# DIO_MCX_Supply.net
KiCad netlist of a schematic drawn in Altium Designer
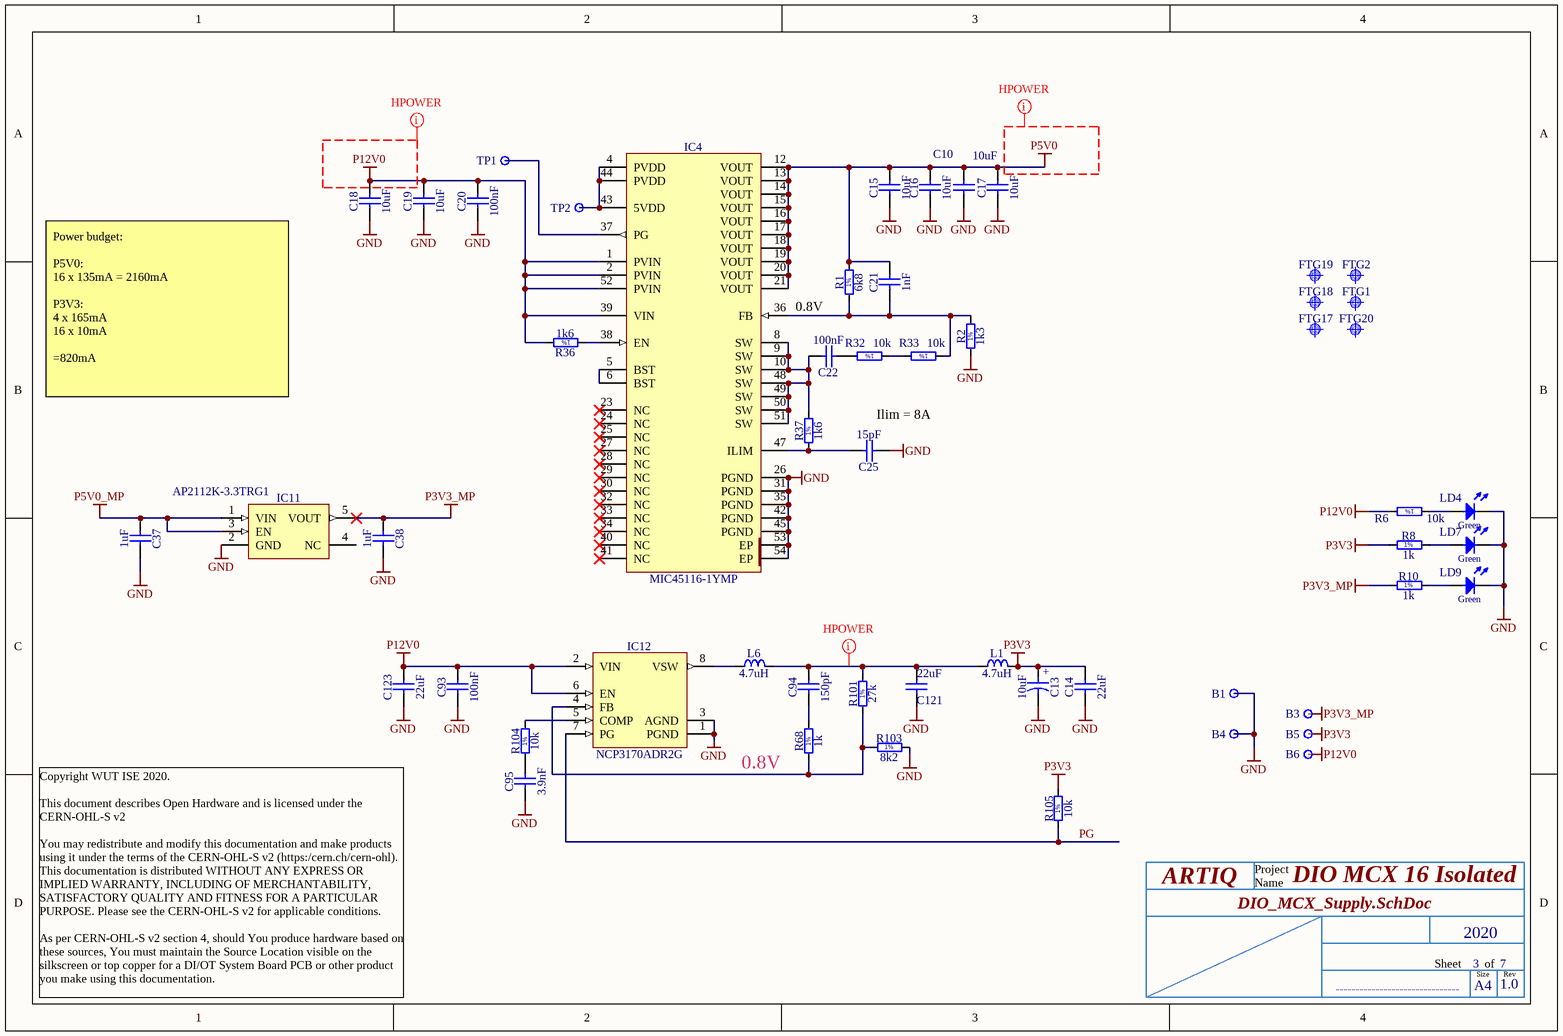
[diagram p0: DIO_MCX_Supply.SchDoc]

(export (version "E")
  (design (tool "Eeschema 10.0.6"))
  (components
    (comp (ref "B1")
      (value "Plated Hole")
      (footprint "c130h60")
      (description "Single Terminal Socket")
      (fields (field (name "PART NUMBER") "PLATED_HOLE0.6_PAD1.3") (field (name "AUTHOR") "CERN DEM MR"))
      (libsource (lib "Eletro-mechanical") (part "Single Terminal Socket"))
    )
    (comp (ref "B3")
      (value "Plated Hole")
      (footprint "c130h60")
      (description "Single Terminal Socket")
      (fields (field (name "PART NUMBER") "PLATED_HOLE0.6_PAD1.3") (field (name "AUTHOR") "CERN DEM MR"))
      (libsource (lib "Eletro-mechanical") (part "Single Terminal Socket"))
    )
    (comp (ref "B4")
      (value "Plated Hole")
      (footprint "c130h60")
      (description "Single Terminal Socket")
      (fields (field (name "PART NUMBER") "PLATED_HOLE0.6_PAD1.3") (field (name "AUTHOR") "CERN DEM MR"))
      (libsource (lib "Eletro-mechanical") (part "Single Terminal Socket"))
    )
    (comp (ref "B5")
      (value "Plated Hole")
      (footprint "c130h60")
      (description "Single Terminal Socket")
      (fields (field (name "PART NUMBER") "PLATED_HOLE0.6_PAD1.3") (field (name "AUTHOR") "CERN DEM MR"))
      (libsource (lib "Eletro-mechanical") (part "Single Terminal Socket"))
    )
    (comp (ref "B6")
      (value "Plated Hole")
      (footprint "c130h60")
      (description "Single Terminal Socket")
      (fields (field (name "PART NUMBER") "PLATED_HOLE0.6_PAD1.3") (field (name "AUTHOR") "CERN DEM MR"))
      (libsource (lib "Eletro-mechanical") (part "Single Terminal Socket"))
    )
    (comp (ref "C10")
      (value "10uF")
      (footprint "CAPC2012X135N")
      (description "Non-polarised capacitor")
      (fields
        (field (name "PART NUMBER") "CC0805_10UF_16V_10%_X5R")
        (field (name "VOLTAGE") "16V")
        (field (name "AUTHOR") "CERN DEM JLC")
      )
      (libsource (lib "Capacitors") (part "Capacitor - non polarized"))
    )
    (comp (ref "C13")
      (value "10uF")
      (footprint "CAPAE430X540N")
      (description "Polarised capacitor")
      (fields
        (field (name "PART NUMBER") "CAE430-540_10UF_16V_20%")
        (field (name "VOLTAGE") "16V")
        (field (name "AUTHOR") "CERN DEM JLC")
      )
      (libsource (lib "Capacitors") (part "Capacitor - polarized"))
    )
    (comp (ref "C14")
      (value "22uF")
      (footprint "CAPC2012X135N")
      (description "Non-polarised capacitor")
      (fields
        (field (name "PART NUMBER") "CC0805_22UF_16V_10%_X5R")
        (field (name "VOLTAGE") "16V")
        (field (name "AUTHOR") "CERN DEM JLC")
      )
      (libsource (lib "Capacitors") (part "Capacitor - non polarized"))
    )
    (comp (ref "C15")
      (value "10uF")
      (footprint "CAPC2012X135N")
      (description "Non-polarised capacitor")
      (fields
        (field (name "PART NUMBER") "CC0805_10UF_16V_10%_X5R")
        (field (name "VOLTAGE") "16V")
        (field (name "AUTHOR") "CERN DEM JLC")
      )
      (libsource (lib "Capacitors") (part "Capacitor - non polarized"))
    )
    (comp (ref "C16")
      (value "10uF")
      (footprint "CAPC2012X135N")
      (description "Non-polarised capacitor")
      (fields
        (field (name "PART NUMBER") "CC0805_10UF_16V_10%_X5R")
        (field (name "VOLTAGE") "16V")
        (field (name "AUTHOR") "CERN DEM JLC")
      )
      (libsource (lib "Capacitors") (part "Capacitor - non polarized"))
    )
    (comp (ref "C17")
      (value "10uF")
      (footprint "CAPC2012X135N")
      (description "Non-polarised capacitor")
      (fields
        (field (name "PART NUMBER") "CC0805_10UF_16V_10%_X5R")
        (field (name "VOLTAGE") "16V")
        (field (name "AUTHOR") "CERN DEM JLC")
      )
      (libsource (lib "Capacitors") (part "Capacitor - non polarized"))
    )
    (comp (ref "C18")
      (value "10uF")
      (footprint "CAPC2012X135N")
      (description "Non-polarised capacitor")
      (fields
        (field (name "PART NUMBER") "CC0805_10UF_16V_10%_X5R")
        (field (name "VOLTAGE") "16V")
        (field (name "AUTHOR") "CERN DEM JLC")
      )
      (libsource (lib "Capacitors") (part "Capacitor - non polarized"))
    )
    (comp (ref "C19")
      (value "10uF")
      (footprint "CAPC2012X135N")
      (description "Non-polarised capacitor")
      (fields
        (field (name "PART NUMBER") "CC0805_10UF_16V_10%_X5R")
        (field (name "VOLTAGE") "16V")
        (field (name "AUTHOR") "CERN DEM JLC")
      )
      (libsource (lib "Capacitors") (part "Capacitor - non polarized"))
    )
    (comp (ref "C20")
      (value "100nF")
      (footprint "CAPC1005X55N")
      (description "Non-polarised capacitor")
      (fields
        (field (name "PART NUMBER") "CC0402_100NF_16V_10%_X5R")
        (field (name "VOLTAGE") "16V")
        (field (name "AUTHOR") "CERN DEM JLC")
      )
      (libsource (lib "Capacitors") (part "Capacitor - non polarized"))
    )
    (comp (ref "C21")
      (value "1nF")
      (footprint "CAPC1608X87N")
      (description "Non-polarised capacitor")
      (fields
        (field (name "PART NUMBER") "CC0603_1NF_100V_10%_X7R")
        (field (name "VOLTAGE") "100V")
        (field (name "AUTHOR") "CERN DEM JLC")
      )
      (libsource (lib "Capacitors") (part "Capacitor - non polarized"))
    )
    (comp (ref "C22")
      (value "100nF")
      (footprint "CAPC1005X55N")
      (description "Non-polarised capacitor")
      (fields
        (field (name "PART NUMBER") "CC0402_100NF_16V_10%_X5R")
        (field (name "VOLTAGE") "16V")
        (field (name "AUTHOR") "CERN DEM JLC")
      )
      (libsource (lib "Capacitors") (part "Capacitor - non polarized"))
    )
    (comp (ref "C25")
      (value "15pF")
      (footprint "CAPC1005X55N")
      (description "Non-polarised capacitor")
      (fields
        (field (name "PART NUMBER") "CC0402_15PF_50V_5%_C0G")
        (field (name "VOLTAGE") "50V")
        (field (name "AUTHOR") "CERN DEM JLC")
      )
      (libsource (lib "Capacitors") (part "Capacitor - non polarized"))
    )
    (comp (ref "C37")
      (value "1uF")
      (footprint "CAPC1005X55N")
      (description "Non-polarised capacitor")
      (fields
        (field (name "PART NUMBER") "CC0402_1UF_16V_10%_X5R")
        (field (name "VOLTAGE") "16V")
        (field (name "AUTHOR") "CERN DEM JLC")
      )
      (libsource (lib "Capacitors") (part "Capacitor - non polarized"))
    )
    (comp (ref "C38")
      (value "1uF")
      (footprint "CAPC1005X55N")
      (description "Non-polarised capacitor")
      (fields
        (field (name "PART NUMBER") "CC0402_1UF_16V_10%_X5R")
        (field (name "VOLTAGE") "16V")
        (field (name "AUTHOR") "CERN DEM JLC")
      )
      (libsource (lib "Capacitors") (part "Capacitor - non polarized"))
    )
    (comp (ref "C93")
      (value "100nF")
      (footprint "CAPC1005X55N")
      (description "Non-polarised capacitor")
      (fields
        (field (name "PART NUMBER") "CC0402_100NF_16V_10%_X5R")
        (field (name "VOLTAGE") "16V")
        (field (name "AUTHOR") "CERN DEM JLC")
      )
      (libsource (lib "Capacitors") (part "Capacitor - non polarized"))
    )
    (comp (ref "C94")
      (value "150pF")
      (footprint "CAPC1608X87N")
      (description "Non-polarised capacitor")
      (fields
        (field (name "PART NUMBER") "CC0603_150PF_50V_1%_NP0")
        (field (name "VOLTAGE") "50V")
        (field (name "AUTHOR") "CERN DEM MR")
      )
      (libsource (lib "Capacitors") (part "Capacitor - non polarized"))
    )
    (comp (ref "C95")
      (value "3.9nF")
      (footprint "CAPC1608X87N")
      (description "Non-polarised capacitor")
      (fields
        (field (name "PART NUMBER") "CC0603_3.9NF_50V_5%_X7R")
        (field (name "VOLTAGE") "50V")
        (field (name "AUTHOR") "CERN DEM JLC")
      )
      (libsource (lib "Capacitors") (part "Capacitor - non polarized"))
    )
    (comp (ref "C121")
      (value "22uF")
      (footprint "CAPC2012X135N")
      (description "Non-polarised capacitor")
      (fields
        (field (name "PART NUMBER") "CC0805_22UF_16V_10%_X5R")
        (field (name "VOLTAGE") "16V")
        (field (name "AUTHOR") "CERN DEM JLC")
      )
      (libsource (lib "Capacitors") (part "Capacitor - non polarized"))
    )
    (comp (ref "C123")
      (value "22uF")
      (footprint "CAPC2012X135N")
      (description "Non-polarised capacitor")
      (fields
        (field (name "PART NUMBER") "CC0805_22UF_16V_10%_X5R")
        (field (name "VOLTAGE") "16V")
        (field (name "AUTHOR") "CERN DEM JLC")
      )
      (libsource (lib "Capacitors") (part "Capacitor - non polarized"))
    )
    (comp (ref "FTG1")
      (value "Use only in PCB")
      (footprint "FIDUCIAL_TOP_C100-200")
      (description "Fiducial Target")
      (fields (field (name "PART NUMBER") "FIDUCIAL_TARGET_C100-200") (field (name "AUTHOR") "CERN DEM JLC"))
      (libsource (lib "Eletro-mechanical") (part "Fiducial Target"))
    )
    (comp (ref "FTG2")
      (value "Use only in PCB")
      (footprint "FIDUCIAL_TOP_C100-200")
      (description "Fiducial Target")
      (fields (field (name "PART NUMBER") "FIDUCIAL_TARGET_C100-200") (field (name "AUTHOR") "CERN DEM JLC"))
      (libsource (lib "Eletro-mechanical") (part "Fiducial Target"))
    )
    (comp (ref "FTG17")
      (value "Use only in PCB")
      (footprint "FIDUCIAL_TOP_C100-200")
      (description "Fiducial Target")
      (fields (field (name "PART NUMBER") "FIDUCIAL_TARGET_C100-200") (field (name "AUTHOR") "CERN DEM JLC"))
      (libsource (lib "Eletro-mechanical") (part "Fiducial Target"))
    )
    (comp (ref "FTG18")
      (value "Use only in PCB")
      (footprint "FIDUCIAL_TOP_S100-200")
      (description "Fiducial Target")
      (fields (field (name "PART NUMBER") "FIDUCIAL_TARGET_S100-200") (field (name "AUTHOR") "CERN DEM JLC"))
      (libsource (lib "Eletro-mechanical") (part "Fiducial Target"))
    )
    (comp (ref "FTG19")
      (value "Use only in PCB")
      (footprint "FIDUCIAL_TOP_S100-200")
      (description "Fiducial Target")
      (fields (field (name "PART NUMBER") "FIDUCIAL_TARGET_S100-200") (field (name "AUTHOR") "CERN DEM JLC"))
      (libsource (lib "Eletro-mechanical") (part "Fiducial Target"))
    )
    (comp (ref "FTG20")
      (value "Use only in PCB")
      (footprint "FIDUCIAL_TOP_S100-200")
      (description "Fiducial Target")
      (fields (field (name "PART NUMBER") "FIDUCIAL_TARGET_S100-200") (field (name "AUTHOR") "CERN DEM JLC"))
      (libsource (lib "Eletro-mechanical") (part "Fiducial Target"))
    )
    (comp (ref "IC4")
      (value "MIC45116-1YMP")
      (footprint "MICROCHIP_H3QFN88-52LD-PL-3")
      (description "0.8V to 85% PVIN (4.75-19V), 6A Synchronous Step-Down Regulator Module")
      (fields (field (name "MANUFACTURER") "MICROCHIP TECHNOLOGY") (field (name "AUTHOR") "CERN DEM JMW"))
      (libsource (lib "ICs And Semiconductors") (part "MIC45116"))
    )
    (comp (ref "IC11")
      (value "AP2112K-3.3TRG1")
      (footprint "SOT95P285X140-5N")
      (description "600mA CMOS Low Dropout Linear Regulator with Enable")
      (fields (field (name "MANUFACTURER") "DIODES INCORPORATED") (field (name "AUTHOR") "CERN DEM MR"))
      (libsource (lib "ICs And Semiconductors") (part "AP2112K"))
    )
    (comp (ref "IC12")
      (value "NCP3170ADR2G")
      (footprint "SOIC127P600X175-8N")
      (description "Synchronous PWM Switching Converter")
      (fields (field (name "MANUFACTURER") "ON SEMICONDUCTOR") (field (name "AUTHOR") "CERN DEM MR"))
      (libsource (lib "ICs And Semiconductors") (part "NCP3170ADR2G"))
    )
    (comp (ref "L1")
      (value "4.7uH")
      (footprint "IND_BOURNS_SRU8043")
      (description "Power Shielded  4.7uH 30% 4.6A")
      (fields
        (field (name "PART NUMBER") "IND_4.7UH_30%_BOURNS_SRU8043")
        (field (name "POWER") "4.6A")
        (field (name "AUTHOR") "GK")
      )
      (libsource (lib "Inductors_Transformers") (part "IND_4.7UH_30%_BOURNS_SRU8043"))
    )
    (comp (ref "L6")
      (value "4.7uH")
      (footprint "IND_BOURNS_SRU8043")
      (description "Power Shielded  4.7uH 30% 4.6A")
      (fields
        (field (name "PART NUMBER") "IND_4.7UH_30%_BOURNS_SRU8043")
        (field (name "POWER") "4.6A")
        (field (name "AUTHOR") "GK")
      )
      (libsource (lib "Inductors_Transformers") (part "IND_4.7UH_30%_BOURNS_SRU8043"))
    )
    (comp (ref "LD4")
      (value "Green")
      (footprint "LED_KINGBRIGHT_KPH-1608CGCK")
      (description "LED Green 1C 2A")
      (fields
        (field (name "PART NUMBER") "LED_KINGBRIGHT_KPH-1608CGCK")
        (field (name "MANUFACTURER") "KINGBRIGHT")
        (field (name "AUTHOR") "CERN DEM JLC")
      )
      (libsource (lib "ICs And Semiconductors") (part "LED Green 1C 2A"))
    )
    (comp (ref "LD7")
      (value "Green")
      (footprint "LED_KINGBRIGHT_KPH-1608CGCK")
      (description "LED Green 1C 2A")
      (fields
        (field (name "PART NUMBER") "LED_KINGBRIGHT_KPH-1608CGCK")
        (field (name "MANUFACTURER") "KINGBRIGHT")
        (field (name "AUTHOR") "CERN DEM JLC")
      )
      (libsource (lib "ICs And Semiconductors") (part "LED Green 1C 2A"))
    )
    (comp (ref "LD9")
      (value "Green")
      (footprint "LED_KINGBRIGHT_KPH-1608CGCK")
      (description "LED Green 1C 2A")
      (fields
        (field (name "PART NUMBER") "LED_KINGBRIGHT_KPH-1608CGCK")
        (field (name "MANUFACTURER") "KINGBRIGHT")
        (field (name "AUTHOR") "CERN DEM JLC")
      )
      (libsource (lib "ICs And Semiconductors") (part "LED Green 1C 2A"))
    )
    (comp (ref "R1")
      (value "6k8")
      (footprint "RESC1005X40N")
      (description "Resistor - 1%")
      (fields
        (field (name "PART NUMBER") "R0402_6K8_1%_0.0625W_100PPM")
        (field (name "POWER") "0.0625W")
        (field (name "AUTHOR") "CERN DEM JLC")
      )
      (libsource (lib "Resistors") (part "Resistor - 1%"))
    )
    (comp (ref "R2")
      (value "1k3")
      (footprint "RESC1608X55N")
      (description "Resistor - 1%")
      (fields
        (field (name "PART NUMBER") "R0603_1K3_1%_0.1W_100PPM")
        (field (name "POWER") "0.1W")
        (field (name "AUTHOR") "CERN DEM JLC")
      )
      (libsource (lib "Resistors") (part "Resistor - 1%"))
    )
    (comp (ref "R6")
      (value "10k")
      (footprint "RESC1005X40N")
      (description "Resistor - 1%")
      (fields
        (field (name "PART NUMBER") "R0402_10K_1%_0.0625W_100PPM")
        (field (name "POWER") "0.0625W")
        (field (name "AUTHOR") "CERN DEM JLC")
      )
      (libsource (lib "Resistors") (part "Resistor - 1%"))
    )
    (comp (ref "R8")
      (value "1k")
      (footprint "RESC1005X40N")
      (description "Resistor - 1%")
      (fields
        (field (name "PART NUMBER") "R0402_1K_1%_0.0625W_100PPM")
        (field (name "POWER") "0.0625W")
        (field (name "AUTHOR") "CERN DEM JLC")
      )
      (libsource (lib "Resistors") (part "Resistor - 1%"))
    )
    (comp (ref "R10")
      (value "1k")
      (footprint "RESC1005X40N")
      (description "Resistor - 1%")
      (fields
        (field (name "PART NUMBER") "R0402_1K_1%_0.0625W_100PPM")
        (field (name "POWER") "0.0625W")
        (field (name "AUTHOR") "CERN DEM JLC")
      )
      (libsource (lib "Resistors") (part "Resistor - 1%"))
    )
    (comp (ref "R32")
      (value "10k")
      (footprint "RESC1005X40N")
      (description "Resistor - 1%")
      (fields
        (field (name "PART NUMBER") "R0402_10K_1%_0.0625W_100PPM")
        (field (name "POWER") "0.0625W")
        (field (name "AUTHOR") "CERN DEM JLC")
      )
      (libsource (lib "Resistors") (part "Resistor - 1%"))
    )
    (comp (ref "R33")
      (value "10k")
      (footprint "RESC1005X40N")
      (description "Resistor - 1%")
      (fields
        (field (name "PART NUMBER") "R0402_10K_1%_0.0625W_100PPM")
        (field (name "POWER") "0.0625W")
        (field (name "AUTHOR") "CERN DEM JLC")
      )
      (libsource (lib "Resistors") (part "Resistor - 1%"))
    )
    (comp (ref "R36")
      (value "1k6")
      (footprint "RESC1005X40N")
      (description "Resistor - 1%")
      (fields
        (field (name "PART NUMBER") "R0402_1K6_1%_0.0625W_100PPM")
        (field (name "POWER") "0.0625W")
        (field (name "AUTHOR") "CERN DEM JLC")
      )
      (libsource (lib "Resistors") (part "Resistor - 1%"))
    )
    (comp (ref "R37")
      (value "1k6")
      (footprint "RESC1005X40N")
      (description "Resistor - 1%")
      (fields
        (field (name "PART NUMBER") "R0402_1K6_1%_0.0625W_100PPM")
        (field (name "POWER") "0.0625W")
        (field (name "AUTHOR") "CERN DEM JLC")
      )
      (libsource (lib "Resistors") (part "Resistor - 1%"))
    )
    (comp (ref "R68")
      (value "1k")
      (footprint "RESC1005X40N")
      (description "Resistor - 1%")
      (fields
        (field (name "PART NUMBER") "R0402_1K_1%_0.0625W_100PPM")
        (field (name "POWER") "0.0625W")
        (field (name "AUTHOR") "CERN DEM JLC")
      )
      (libsource (lib "Resistors") (part "Resistor - 1%"))
    )
    (comp (ref "R101")
      (value "27k")
      (footprint "RESC1005X40N")
      (description "Resistor - 1%")
      (fields
        (field (name "PART NUMBER") "R0402_27K_1%_0.0625W_100PPM")
        (field (name "POWER") "0.0625W")
        (field (name "AUTHOR") "CERN DEM JLC")
      )
      (libsource (lib "Resistors") (part "Resistor - 1%"))
    )
    (comp (ref "R103")
      (value "8k2")
      (footprint "RESC1005X40N")
      (description "Resistor - 1%")
      (fields
        (field (name "PART NUMBER") "R0402_8K2_1%_0.0625W_100PPM")
        (field (name "POWER") "0.0625W")
        (field (name "AUTHOR") "CERN DEM JLC")
      )
      (libsource (lib "Resistors") (part "Resistor - 1%"))
    )
    (comp (ref "R104")
      (value "10k")
      (footprint "RESC1005X40N")
      (description "Resistor - 1%")
      (fields
        (field (name "PART NUMBER") "R0402_10K_1%_0.0625W_100PPM")
        (field (name "POWER") "0.0625W")
        (field (name "AUTHOR") "CERN DEM JLC")
      )
      (libsource (lib "Resistors") (part "Resistor - 1%"))
    )
    (comp (ref "R105")
      (value "10k")
      (footprint "RESC1005X40N")
      (description "Resistor - 1%")
      (fields
        (field (name "PART NUMBER") "R0402_10K_1%_0.0625W_100PPM")
        (field (name "POWER") "0.0625W")
        (field (name "AUTHOR") "CERN DEM JLC")
      )
      (libsource (lib "Resistors") (part "Resistor - 1%"))
    )
    (comp (ref "TP1")
      (value "Test Point")
      (footprint "TPS127")
      (fields (field (name "PART NUMBER") "SMD_PAD_1.27X1.27MM") (field (name "AUTHOR") "CERN DEM JLC"))
      (libsource (lib "Eletro-mechanical") (part "Test Point"))
    )
    (comp (ref "TP2")
      (value "Test Point")
      (footprint "TPS127")
      (fields (field (name "PART NUMBER") "SMD_PAD_1.27X1.27MM") (field (name "AUTHOR") "CERN DEM JLC"))
      (libsource (lib "Eletro-mechanical") (part "Test Point"))
    )
  )
  (nets
    (net (code "1") (name "/PG") (class "Default")
      (node (ref "IC12") (pin "7") (pinfunction "PG_7") (pintype "input"))
      (node (ref "R105") (pin "1") (pinfunction "1_1") (pintype "passive"))
    )
    (net (code "2") (name "GND") (class "Default")
      (node (ref "B1") (pin "1") (pinfunction "1_1") (pintype "bidirectional"))
      (node (ref "B4") (pin "1") (pinfunction "1_1") (pintype "bidirectional"))
      (node (ref "C10") (pin "1") (pinfunction "1_1") (pintype "passive"))
      (node (ref "C121") (pin "1") (pinfunction "1_1") (pintype "passive"))
      (node (ref "C123") (pin "1") (pinfunction "1_1") (pintype "passive"))
      (node (ref "C13") (pin "2") (pinfunction "2_2") (pintype "passive"))
      (node (ref "C14") (pin "1") (pinfunction "1_1") (pintype "passive"))
      (node (ref "C15") (pin "1") (pinfunction "1_1") (pintype "passive"))
      (node (ref "C16") (pin "1") (pinfunction "1_1") (pintype "passive"))
      (node (ref "C17") (pin "1") (pinfunction "1_1") (pintype "passive"))
      (node (ref "C18") (pin "1") (pinfunction "1_1") (pintype "passive"))
      (node (ref "C19") (pin "1") (pinfunction "1_1") (pintype "passive"))
      (node (ref "C20") (pin "1") (pinfunction "1_1") (pintype "passive"))
      (node (ref "C25") (pin "1") (pinfunction "1_1") (pintype "passive"))
      (node (ref "C37") (pin "1") (pinfunction "1_1") (pintype "passive"))
      (node (ref "C38") (pin "1") (pinfunction "1_1") (pintype "passive"))
      (node (ref "C93") (pin "1") (pinfunction "1_1") (pintype "passive"))
      (node (ref "C95") (pin "1") (pinfunction "1_1") (pintype "passive"))
      (node (ref "IC11") (pin "2") (pinfunction "GND_2") (pintype "power_in"))
      (node (ref "IC12") (pin "1") (pinfunction "PGND_1") (pintype "power_in"))
      (node (ref "IC12") (pin "3") (pinfunction "AGND_3") (pintype "power_in"))
      (node (ref "IC4") (pin "26") (pinfunction "PGND_26") (pintype "power_in"))
      (node (ref "IC4") (pin "31") (pinfunction "PGND_31") (pintype "power_in"))
      (node (ref "IC4") (pin "35") (pinfunction "PGND_35") (pintype "power_in"))
      (node (ref "IC4") (pin "42") (pinfunction "PGND_42") (pintype "power_in"))
      (node (ref "IC4") (pin "45") (pinfunction "PGND_45") (pintype "power_in"))
      (node (ref "IC4") (pin "53") (pinfunction "EP_53") (pintype "power_in"))
      (node (ref "IC4") (pin "54") (pinfunction "EP_54") (pintype "power_in"))
      (node (ref "LD4") (pin "1") (pinfunction "C_1") (pintype "passive"))
      (node (ref "LD7") (pin "1") (pinfunction "C_1") (pintype "passive"))
      (node (ref "LD9") (pin "1") (pinfunction "C_1") (pintype "passive"))
      (node (ref "R103") (pin "2") (pinfunction "2_2") (pintype "passive"))
      (node (ref "R2") (pin "1") (pinfunction "1_1") (pintype "passive"))
    )
    (net (code "3") (name "Net-(C22-Pad1)") (class "Default")
      (node (ref "C22") (pin "1") (pinfunction "1_1") (pintype "passive"))
      (node (ref "R32") (pin "2") (pinfunction "2_2") (pintype "passive"))
    )
    (net (code "4") (name "Net-(C22-Pad2)") (class "Default")
      (node (ref "C22") (pin "2") (pinfunction "2_2") (pintype "passive"))
      (node (ref "IC4") (pin "10") (pinfunction "SW_10") (pintype "passive"))
      (node (ref "IC4") (pin "48") (pinfunction "SW_48") (pintype "passive"))
      (node (ref "IC4") (pin "49") (pinfunction "SW_49") (pintype "passive"))
      (node (ref "IC4") (pin "50") (pinfunction "SW_50") (pintype "passive"))
      (node (ref "IC4") (pin "51") (pinfunction "SW_51") (pintype "passive"))
      (node (ref "IC4") (pin "8") (pinfunction "SW_8") (pintype "passive"))
      (node (ref "IC4") (pin "9") (pinfunction "SW_9") (pintype "passive"))
      (node (ref "R37") (pin "2") (pinfunction "2_2") (pintype "passive"))
    )
    (net (code "5") (name "Net-(C94-Pad1)") (class "Default")
      (node (ref "C94") (pin "1") (pinfunction "1_1") (pintype "passive"))
      (node (ref "R68") (pin "2") (pinfunction "2_2") (pintype "passive"))
    )
    (net (code "6") (name "Net-(C95-Pad2)") (class "Default")
      (node (ref "C95") (pin "2") (pinfunction "2_2") (pintype "passive"))
      (node (ref "R104") (pin "1") (pinfunction "1_1") (pintype "passive"))
    )
    (net (code "7") (name "Net-(C121-Pad2)") (class "Default")
      (node (ref "C121") (pin "2") (pinfunction "2_2") (pintype "passive"))
      (node (ref "C94") (pin "2") (pinfunction "2_2") (pintype "passive"))
      (node (ref "L1") (pin "1") (pinfunction "1_1") (pintype "passive"))
      (node (ref "L6") (pin "2") (pinfunction "2_2") (pintype "passive"))
      (node (ref "R101") (pin "2") (pinfunction "2_2") (pintype "passive"))
    )
    (net (code "8") (name "Net-(IC4-5VDD)") (class "Default")
      (node (ref "IC4") (pin "4") (pinfunction "PVDD_4") (pintype "power_in"))
      (node (ref "IC4") (pin "43") (pinfunction "5VDD_43") (pintype "power_in"))
      (node (ref "IC4") (pin "44") (pinfunction "PVDD_44") (pintype "power_in"))
      (node (ref "TP2") (pin "1") (pinfunction "1_1") (pintype "bidirectional"))
    )
    (net (code "9") (name "Net-(IC4-BST-Pad5)") (class "Default")
      (node (ref "IC4") (pin "5") (pinfunction "BST_5") (pintype "passive"))
      (node (ref "IC4") (pin "6") (pinfunction "BST_6") (pintype "passive"))
    )
    (net (code "10") (name "Net-(IC4-EN)") (class "Default")
      (node (ref "IC4") (pin "38") (pinfunction "EN_38") (pintype "input"))
      (node (ref "R36") (pin "1") (pinfunction "1_1") (pintype "passive"))
    )
    (net (code "11") (name "Net-(IC4-FB)") (class "Default")
      (node (ref "C21") (pin "1") (pinfunction "1_1") (pintype "passive"))
      (node (ref "IC4") (pin "36") (pinfunction "FB_36") (pintype "input"))
      (node (ref "R1") (pin "1") (pinfunction "1_1") (pintype "passive"))
      (node (ref "R2") (pin "2") (pinfunction "2_2") (pintype "passive"))
      (node (ref "R33") (pin "1") (pinfunction "1_1") (pintype "passive"))
    )
    (net (code "12") (name "Net-(IC4-ILIM)") (class "Default")
      (node (ref "C25") (pin "2") (pinfunction "2_2") (pintype "passive"))
      (node (ref "IC4") (pin "47") (pinfunction "ILIM_47") (pintype "passive"))
      (node (ref "R37") (pin "1") (pinfunction "1_1") (pintype "passive"))
    )
    (net (code "13") (name "Net-(IC4-PG)") (class "Default")
      (node (ref "IC4") (pin "37") (pinfunction "PG_37") (pintype "output"))
      (node (ref "TP1") (pin "1") (pinfunction "1_1") (pintype "bidirectional"))
    )
    (net (code "14") (name "Net-(IC12-COMP)") (class "Default")
      (node (ref "IC12") (pin "5") (pinfunction "COMP_5") (pintype "input"))
      (node (ref "R104") (pin "2") (pinfunction "2_2") (pintype "passive"))
    )
    (net (code "15") (name "Net-(IC12-FB)") (class "Default")
      (node (ref "IC12") (pin "4") (pinfunction "FB_4") (pintype "input"))
      (node (ref "R101") (pin "1") (pinfunction "1_1") (pintype "passive"))
      (node (ref "R103") (pin "1") (pinfunction "1_1") (pintype "passive"))
      (node (ref "R68") (pin "1") (pinfunction "1_1") (pintype "passive"))
    )
    (net (code "16") (name "Net-(IC12-VSW)") (class "Default")
      (node (ref "IC12") (pin "8") (pinfunction "VSW_8") (pintype "output"))
      (node (ref "L6") (pin "1") (pinfunction "1_1") (pintype "passive"))
    )
    (net (code "17") (name "Net-(LD4-A)") (class "Default")
      (node (ref "LD4") (pin "2") (pinfunction "A_2") (pintype "passive"))
      (node (ref "R6") (pin "1") (pinfunction "1_1") (pintype "passive"))
    )
    (net (code "18") (name "Net-(LD7-A)") (class "Default")
      (node (ref "LD7") (pin "2") (pinfunction "A_2") (pintype "passive"))
      (node (ref "R8") (pin "2") (pinfunction "2_2") (pintype "passive"))
    )
    (net (code "19") (name "Net-(LD9-A)") (class "Default")
      (node (ref "LD9") (pin "2") (pinfunction "A_2") (pintype "passive"))
      (node (ref "R10") (pin "2") (pinfunction "2_2") (pintype "passive"))
    )
    (net (code "20") (name "Net-(R32-Pad1)") (class "Default")
      (node (ref "R32") (pin "1") (pinfunction "1_1") (pintype "passive"))
      (node (ref "R33") (pin "2") (pinfunction "2_2") (pintype "passive"))
    )
    (net (code "21") (name "P3V3") (class "Default")
      (node (ref "B5") (pin "1") (pinfunction "1_1") (pintype "bidirectional"))
      (node (ref "C13") (pin "1") (pinfunction "1_1") (pintype "passive"))
      (node (ref "C14") (pin "2") (pinfunction "2_2") (pintype "passive"))
      (node (ref "L1") (pin "2") (pinfunction "2_2") (pintype "passive"))
      (node (ref "R105") (pin "2") (pinfunction "2_2") (pintype "passive"))
      (node (ref "R8") (pin "1") (pinfunction "1_1") (pintype "passive"))
    )
    (net (code "22") (name "P3V3_MP") (class "Default")
      (node (ref "B3") (pin "1") (pinfunction "1_1") (pintype "bidirectional"))
      (node (ref "C38") (pin "2") (pinfunction "2_2") (pintype "passive"))
      (node (ref "IC11") (pin "5") (pinfunction "VOUT_5") (pintype "output"))
      (node (ref "R10") (pin "1") (pinfunction "1_1") (pintype "passive"))
    )
    (net (code "23") (name "P5V0") (class "Default")
      (node (ref "C10") (pin "2") (pinfunction "2_2") (pintype "passive"))
      (node (ref "C15") (pin "2") (pinfunction "2_2") (pintype "passive"))
      (node (ref "C16") (pin "2") (pinfunction "2_2") (pintype "passive"))
      (node (ref "C17") (pin "2") (pinfunction "2_2") (pintype "passive"))
      (node (ref "C21") (pin "2") (pinfunction "2_2") (pintype "passive"))
      (node (ref "IC4") (pin "12") (pinfunction "VOUT_12") (pintype "power_in"))
      (node (ref "IC4") (pin "13") (pinfunction "VOUT_13") (pintype "power_in"))
      (node (ref "IC4") (pin "14") (pinfunction "VOUT_14") (pintype "power_in"))
      (node (ref "IC4") (pin "15") (pinfunction "VOUT_15") (pintype "power_in"))
      (node (ref "IC4") (pin "16") (pinfunction "VOUT_16") (pintype "power_in"))
      (node (ref "IC4") (pin "17") (pinfunction "VOUT_17") (pintype "power_in"))
      (node (ref "IC4") (pin "18") (pinfunction "VOUT_18") (pintype "power_in"))
      (node (ref "IC4") (pin "19") (pinfunction "VOUT_19") (pintype "power_in"))
      (node (ref "IC4") (pin "20") (pinfunction "VOUT_20") (pintype "power_in"))
      (node (ref "IC4") (pin "21") (pinfunction "VOUT_21") (pintype "power_in"))
      (node (ref "R1") (pin "2") (pinfunction "2_2") (pintype "passive"))
    )
    (net (code "24") (name "P5V0_MP") (class "Default")
      (node (ref "C37") (pin "2") (pinfunction "2_2") (pintype "passive"))
      (node (ref "IC11") (pin "1") (pinfunction "VIN_1") (pintype "input"))
      (node (ref "IC11") (pin "3") (pinfunction "EN_3") (pintype "input"))
    )
    (net (code "25") (name "P12V0") (class "Default")
      (node (ref "B6") (pin "1") (pinfunction "1_1") (pintype "bidirectional"))
      (node (ref "C123") (pin "2") (pinfunction "2_2") (pintype "passive"))
      (node (ref "C18") (pin "2") (pinfunction "2_2") (pintype "passive"))
      (node (ref "C19") (pin "2") (pinfunction "2_2") (pintype "passive"))
      (node (ref "C20") (pin "2") (pinfunction "2_2") (pintype "passive"))
      (node (ref "C93") (pin "2") (pinfunction "2_2") (pintype "passive"))
      (node (ref "IC12") (pin "2") (pinfunction "VIN_2") (pintype "input"))
      (node (ref "IC12") (pin "6") (pinfunction "EN_6") (pintype "input"))
      (node (ref "IC4") (pin "1") (pinfunction "PVIN_1") (pintype "power_in"))
      (node (ref "IC4") (pin "2") (pinfunction "PVIN_2") (pintype "power_in"))
      (node (ref "IC4") (pin "39") (pinfunction "VIN_39") (pintype "power_in"))
      (node (ref "IC4") (pin "52") (pinfunction "PVIN_52") (pintype "power_in"))
      (node (ref "R36") (pin "2") (pinfunction "2_2") (pintype "passive"))
      (node (ref "R6") (pin "2") (pinfunction "2_2") (pintype "passive"))
    )
    (net (code "26") (name "unconnected-(IC4-NC-Pad23)") (class "Default")
      (node (ref "IC4") (pin "23") (pinfunction "NC_23") (pintype "passive+no_connect"))
    )
    (net (code "27") (name "unconnected-(IC4-NC-Pad24)") (class "Default")
      (node (ref "IC4") (pin "24") (pinfunction "NC_24") (pintype "passive+no_connect"))
    )
    (net (code "28") (name "unconnected-(IC4-NC-Pad25)") (class "Default")
      (node (ref "IC4") (pin "25") (pinfunction "NC_25") (pintype "passive+no_connect"))
    )
    (net (code "29") (name "unconnected-(IC4-NC-Pad27)") (class "Default")
      (node (ref "IC4") (pin "27") (pinfunction "NC_27") (pintype "passive+no_connect"))
    )
    (net (code "30") (name "unconnected-(IC4-NC-Pad28)") (class "Default")
      (node (ref "IC4") (pin "28") (pinfunction "NC_28") (pintype "passive+no_connect"))
    )
    (net (code "31") (name "unconnected-(IC4-NC-Pad29)") (class "Default")
      (node (ref "IC4") (pin "29") (pinfunction "NC_29") (pintype "passive+no_connect"))
    )
    (net (code "32") (name "unconnected-(IC4-NC-Pad30)") (class "Default")
      (node (ref "IC4") (pin "30") (pinfunction "NC_30") (pintype "passive+no_connect"))
    )
    (net (code "33") (name "unconnected-(IC4-NC-Pad32)") (class "Default")
      (node (ref "IC4") (pin "32") (pinfunction "NC_32") (pintype "passive+no_connect"))
    )
    (net (code "34") (name "unconnected-(IC4-NC-Pad33)") (class "Default")
      (node (ref "IC4") (pin "33") (pinfunction "NC_33") (pintype "passive+no_connect"))
    )
    (net (code "35") (name "unconnected-(IC4-NC-Pad34)") (class "Default")
      (node (ref "IC4") (pin "34") (pinfunction "NC_34") (pintype "passive+no_connect"))
    )
    (net (code "36") (name "unconnected-(IC4-NC-Pad40)") (class "Default")
      (node (ref "IC4") (pin "40") (pinfunction "NC_40") (pintype "passive+no_connect"))
    )
    (net (code "37") (name "unconnected-(IC4-NC-Pad41)") (class "Default")
      (node (ref "IC4") (pin "41") (pinfunction "NC_41") (pintype "passive+no_connect"))
    )
    (net (code "38") (name "unconnected-(IC11-NC-Pad4)") (class "Default")
      (node (ref "IC11") (pin "4") (pinfunction "NC_4") (pintype "passive"))
    )
  )
)
